# 04_-_CPU_-_SIGNAL_USB_JTAG.net
KiCad netlist of a schematic drawn in Altium Designer
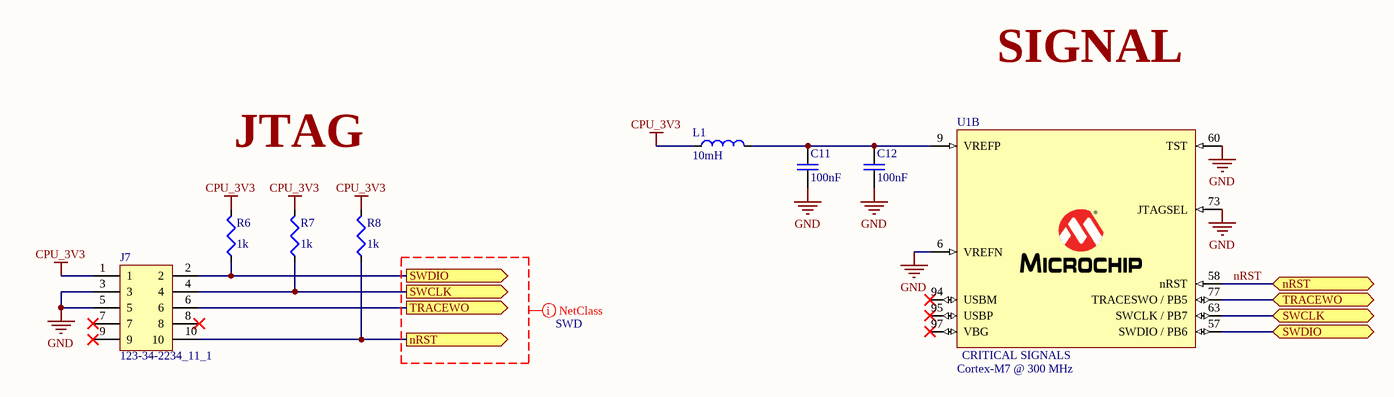
[diagram p0: [04] - CPU - SIGNAL, USB, JTAG.SchDoc]

(export (version "E")
  (design (tool "Eeschema 10.0.6"))
  (components
    (comp (ref "C11")
      (value "100nF")
      (footprint "C0603")
      (description "C0603")
      (fields (field (name "Comment") "02016D104KAT2A"))
      (libsource (lib "Passive components") (part "02016D104KAT2A"))
    )
    (comp (ref "C12")
      (value "100nF")
      (footprint "C0603")
      (description "C0603")
      (fields (field (name "Comment") "02016D104KAT2A"))
      (libsource (lib "Passive components") (part "02016D104KAT2A"))
    )
    (comp (ref "J7")
      (value "123-34-2234_11_1")
      (footprint "Header 2x5 male 1.27mm")
      (description "Header 2x5 male 1.27mm")
      (libsource (lib "Connectors") (part "123-34-2234_11_1"))
    )
    (comp (ref "L1")
      (value "10mH")
      (footprint "Inductor 0603")
      (description "Inductor 0603")
      (fields (field (name "Comment") "MLZ1608A2R2WT"))
      (libsource (lib "Passive components") (part "MLZ1608A2R2WT"))
    )
    (comp (ref "R6")
      (value "1k")
      (footprint "R0603")
      (description "R0603")
      (fields (field (name "Comment") "CPF-A-0603B100KE1"))
      (libsource (lib "Passive components") (part "CPF-A-0603B100KE1"))
    )
    (comp (ref "R7")
      (value "1k")
      (footprint "R0603")
      (description "R0603")
      (fields (field (name "Comment") "CPF-A-0603B100KE1"))
      (libsource (lib "Passive components") (part "CPF-A-0603B100KE1"))
    )
    (comp (ref "R8")
      (value "1k")
      (footprint "R0603")
      (description "R0603")
      (fields (field (name "Comment") "CPF-A-0603B100KE1"))
      (libsource (lib "Passive components") (part "CPF-A-0603B100KE1"))
    )
    (comp (ref "U1")
      (value "Cortex-M7 @ 300 MHz")
      (footprint "ATSAMS70N19A-AN")
      (description "ATSAMS70N19")
      (libsource (lib "Microcontrollers") (part "ATSAMS70N19A-AN"))
    )
  )
  (nets
    (net (code "1") (name "/SWCLK") (class "Default")
      (node (ref "J7") (pin "4") (pinfunction "4_4") (pintype "passive"))
      (node (ref "R7") (pin "1") (pinfunction "1_1") (pintype "passive"))
      (node (ref "U1") (pin "63") (pinfunction "SWCLK_/_PB7_63") (pintype "bidirectional"))
    )
    (net (code "2") (name "/SWDIO") (class "Default")
      (node (ref "J7") (pin "2") (pinfunction "2_2") (pintype "passive"))
      (node (ref "R6") (pin "1") (pinfunction "1_1") (pintype "passive"))
      (node (ref "U1") (pin "57") (pinfunction "SWDIO_/_PB6_57") (pintype "bidirectional"))
    )
    (net (code "3") (name "/TRACEWO") (class "Default")
      (node (ref "J7") (pin "6") (pinfunction "6_6") (pintype "passive"))
      (node (ref "U1") (pin "77") (pinfunction "TRACESWO_/_PB5_77") (pintype "bidirectional"))
    )
    (net (code "4") (name "/nRST") (class "Default")
      (node (ref "J7") (pin "10") (pinfunction "10_10") (pintype "passive"))
      (node (ref "R8") (pin "1") (pinfunction "1_1") (pintype "passive"))
      (node (ref "U1") (pin "58") (pinfunction "nRST_58") (pintype "input"))
    )
    (net (code "5") (name "CPU_3V3") (class "Default")
      (node (ref "J7") (pin "1") (pinfunction "1_1") (pintype "passive"))
      (node (ref "L1") (pin "1") (pinfunction "1_1") (pintype "passive"))
      (node (ref "R6") (pin "2") (pinfunction "2_2") (pintype "passive"))
      (node (ref "R7") (pin "2") (pinfunction "2_2") (pintype "passive"))
      (node (ref "R8") (pin "2") (pinfunction "2_2") (pintype "passive"))
    )
    (net (code "6") (name "GND") (class "Default")
      (node (ref "C11") (pin "1") (pinfunction "1_1") (pintype "passive"))
      (node (ref "C12") (pin "1") (pinfunction "1_1") (pintype "passive"))
      (node (ref "J7") (pin "3") (pinfunction "3_3") (pintype "passive"))
      (node (ref "J7") (pin "5") (pinfunction "5_5") (pintype "passive"))
      (node (ref "U1") (pin "6") (pinfunction "VREFN_6") (pintype "input"))
      (node (ref "U1") (pin "60") (pinfunction "TST_60") (pintype "input"))
      (node (ref "U1") (pin "73") (pinfunction "JTAGSEL_73") (pintype "input"))
    )
    (net (code "7") (name "Net-(U1B-VREFP)") (class "Default")
      (node (ref "C11") (pin "2") (pinfunction "2_2") (pintype "passive"))
      (node (ref "C12") (pin "2") (pinfunction "2_2") (pintype "passive"))
      (node (ref "L1") (pin "2") (pinfunction "2_2") (pintype "passive"))
      (node (ref "U1") (pin "9") (pinfunction "VREFP_9") (pintype "input"))
    )
    (net (code "8") (name "unconnected-(J7-Pad7)") (class "Default")
      (node (ref "J7") (pin "7") (pinfunction "7_7") (pintype "passive+no_connect"))
    )
    (net (code "9") (name "unconnected-(J7-Pad8)") (class "Default")
      (node (ref "J7") (pin "8") (pinfunction "8_8") (pintype "passive+no_connect"))
    )
    (net (code "10") (name "unconnected-(J7-Pad9)") (class "Default")
      (node (ref "J7") (pin "9") (pinfunction "9_9") (pintype "passive+no_connect"))
    )
    (net (code "11") (name "unconnected-(U1B-USBM-Pad94)") (class "Default")
      (node (ref "U1") (pin "94") (pinfunction "USBM_94") (pintype "bidirectional+no_connect"))
    )
    (net (code "12") (name "unconnected-(U1B-USBP-Pad95)") (class "Default")
      (node (ref "U1") (pin "95") (pinfunction "USBP_95") (pintype "bidirectional+no_connect"))
    )
    (net (code "13") (name "unconnected-(U1B-VBG-Pad97)") (class "Default")
      (node (ref "U1") (pin "97") (pinfunction "VBG_97") (pintype "bidirectional+no_connect"))
    )
  )
)
